# Microcontroller_and_Memory.net
KiCad netlist of a schematic drawn in Altium Designer
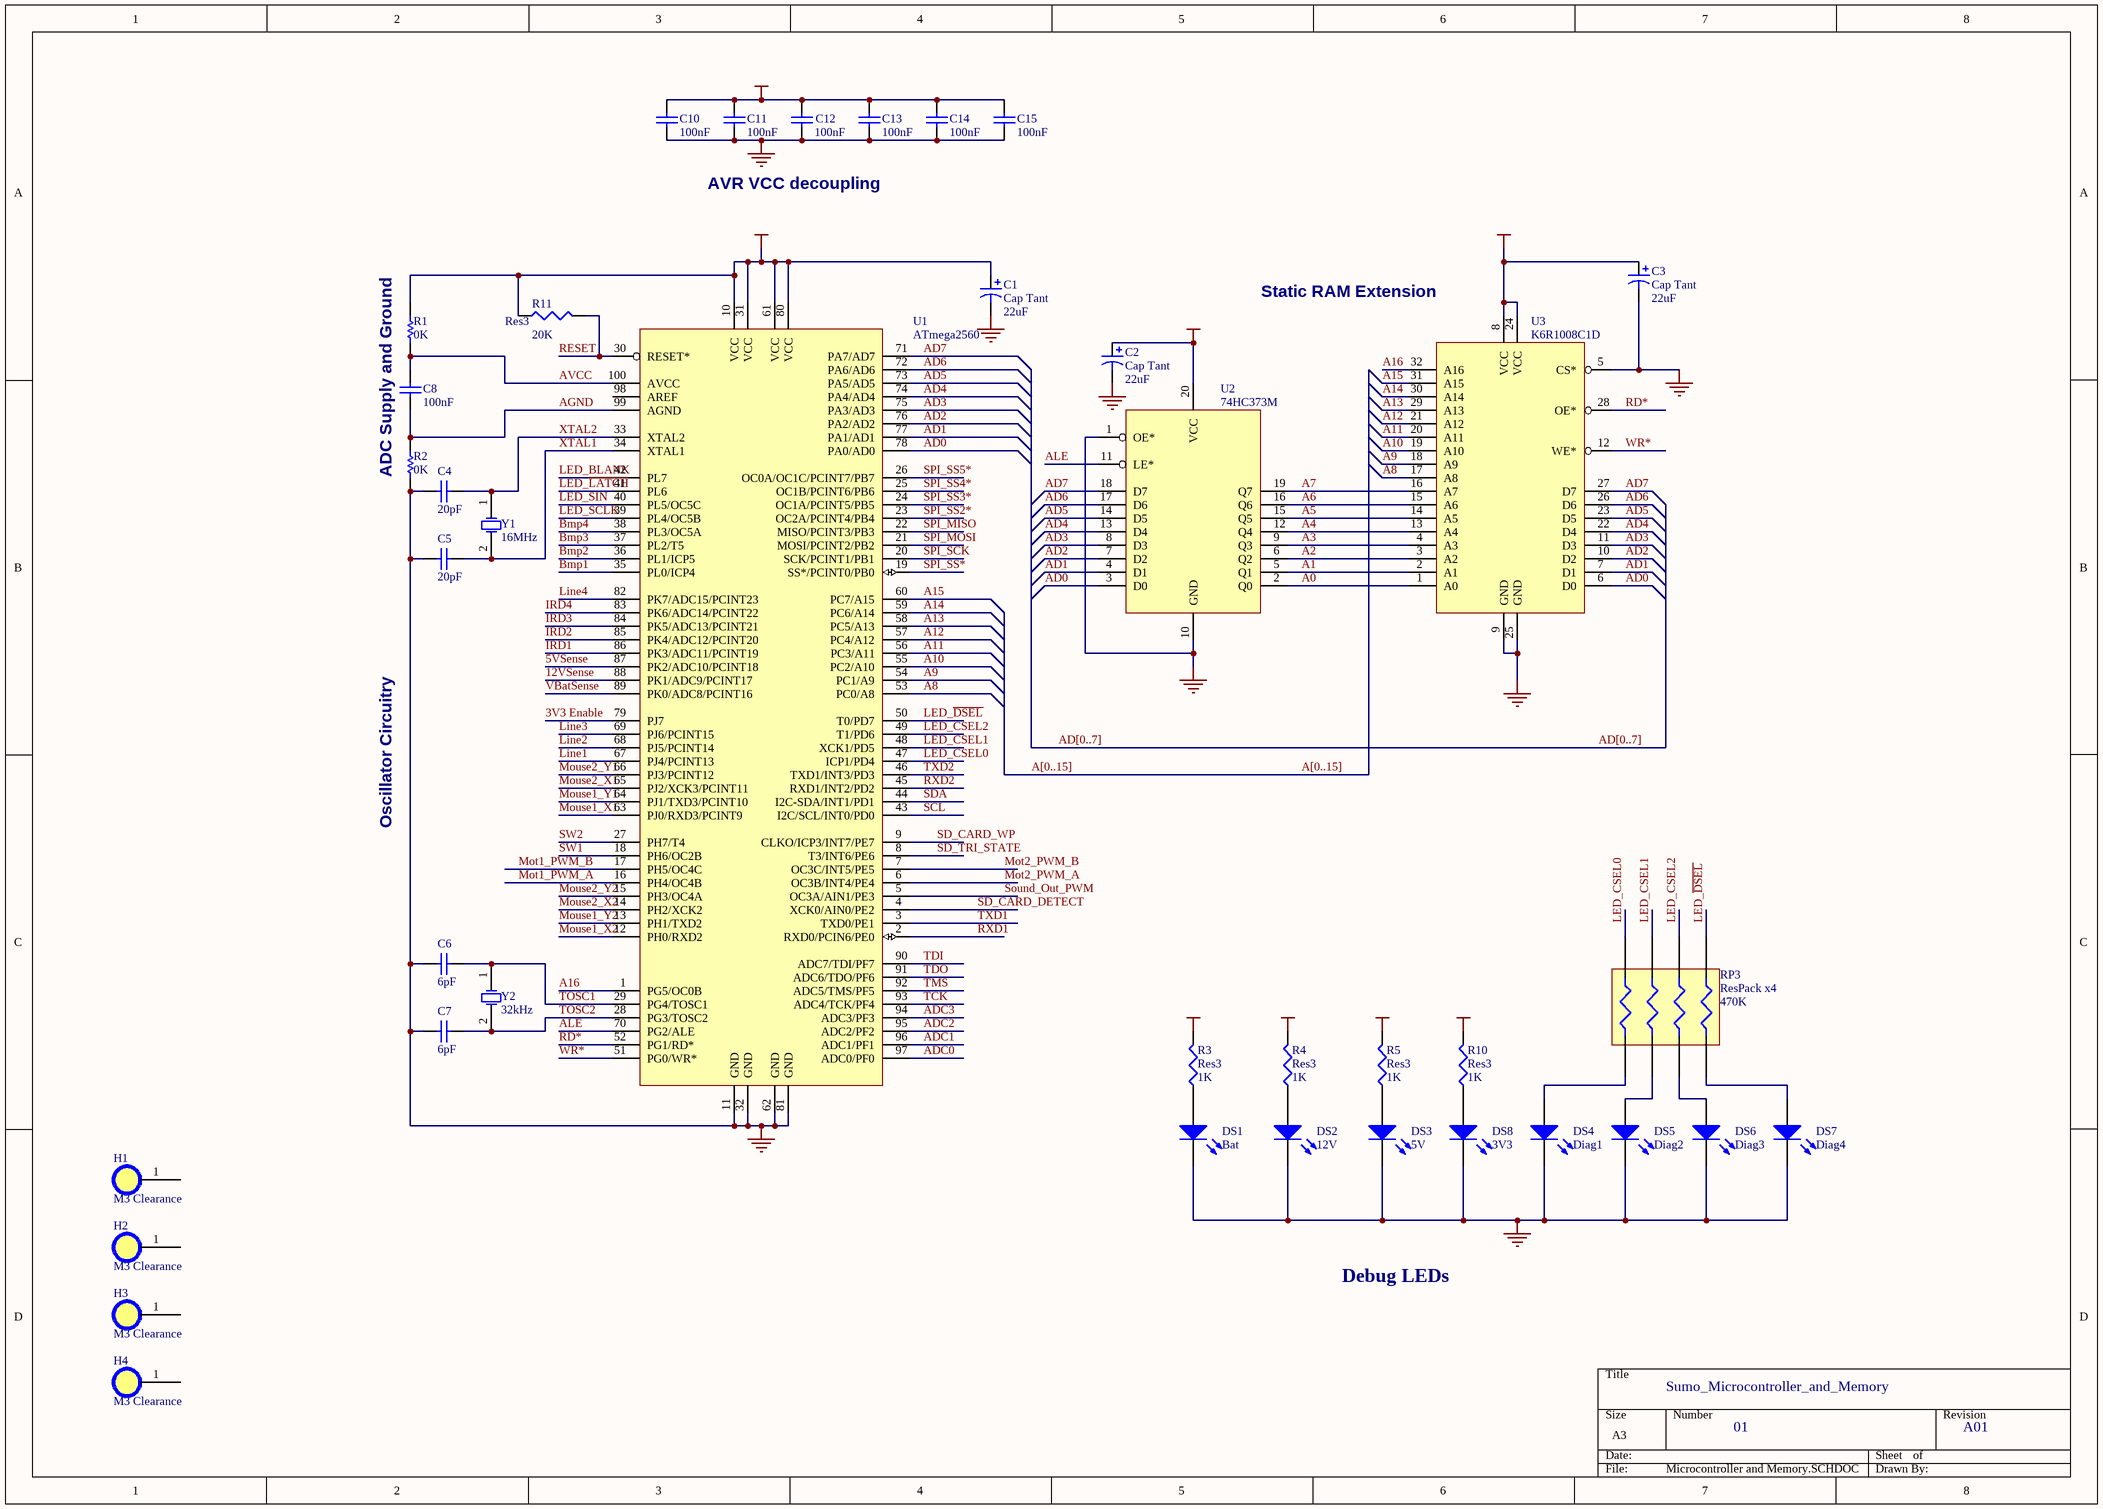
[diagram p0: Microcontroller and Memory.SCHDOC]

(export (version "E")
  (design (tool "Eeschema 10.0.6"))
  (components
    (comp (ref "C1")
      (value "Cap Tant")
      (footprint "CC4532-1812")
      (description "Polarized Capacitor (Axial)")
      (fields (field (name "ALTIUM_VALUE") "22uF") (field (name "PUBLISHER") "Altium Limited"))
      (libsource (lib "Miscellaneous Devices") (part "Cap Pol2"))
    )
    (comp (ref "C2")
      (value "Cap Tant")
      (footprint "CC4532-1812")
      (description "Polarized Capacitor (Axial)")
      (fields (field (name "ALTIUM_VALUE") "22uF") (field (name "PUBLISHER") "Altium Limited"))
      (libsource (lib "Miscellaneous Devices") (part "Cap Pol2"))
    )
    (comp (ref "C3")
      (value "Cap Tant")
      (footprint "CC4532-1812")
      (description "Polarized Capacitor (Axial)")
      (fields (field (name "ALTIUM_VALUE") "22uF") (field (name "PUBLISHER") "Altium Limited"))
      (libsource (lib "Miscellaneous Devices") (part "Cap Pol2"))
    )
    (comp (ref "C4")
      (value "20pF")
      (footprint "CC2012-0805")
      (description "Capacitor")
      (fields (field (name "PUBLISHER") "Altium Limited"))
      (libsource (lib "Miscellaneous Devices") (part "Cap"))
    )
    (comp (ref "C5")
      (value "20pF")
      (footprint "CC2012-0805")
      (description "Capacitor")
      (fields (field (name "PUBLISHER") "Altium Limited"))
      (libsource (lib "Miscellaneous Devices") (part "Cap"))
    )
    (comp (ref "C6")
      (value "6pF")
      (footprint "CC2012-0805")
      (description "Capacitor")
      (fields (field (name "PUBLISHER") "Altium Limited"))
      (libsource (lib "Miscellaneous Devices") (part "Cap"))
    )
    (comp (ref "C7")
      (value "6pF")
      (footprint "CC2012-0805")
      (description "Capacitor")
      (fields (field (name "PUBLISHER") "Altium Limited"))
      (libsource (lib "Miscellaneous Devices") (part "Cap"))
    )
    (comp (ref "C8")
      (value "100nF")
      (footprint "CC2012-0805")
      (description "Capacitor")
      (fields (field (name "PUBLISHER") "Altium Limited"))
      (libsource (lib "Miscellaneous Devices") (part "Cap"))
    )
    (comp (ref "C10")
      (value "100nF")
      (footprint "CC2012-0805")
      (description "Capacitor (Semiconductor SIM Model)")
      (fields (field (name "Comment") "Cap Semi") (field (name "PUBLISHER") "Altium Limited"))
      (libsource (lib "Miscellaneous Devices") (part "Cap Semi"))
    )
    (comp (ref "C11")
      (value "100nF")
      (footprint "CC2012-0805")
      (description "Capacitor (Semiconductor SIM Model)")
      (fields (field (name "Comment") "Cap Semi") (field (name "PUBLISHER") "Altium Limited"))
      (libsource (lib "Miscellaneous Devices") (part "Cap Semi"))
    )
    (comp (ref "C12")
      (value "100nF")
      (footprint "CC2012-0805")
      (description "Capacitor (Semiconductor SIM Model)")
      (fields (field (name "Comment") "Cap Semi") (field (name "PUBLISHER") "Altium Limited"))
      (libsource (lib "Miscellaneous Devices") (part "Cap Semi"))
    )
    (comp (ref "C13")
      (value "100nF")
      (footprint "CC2012-0805")
      (description "Capacitor (Semiconductor SIM Model)")
      (fields (field (name "Comment") "Cap Semi") (field (name "PUBLISHER") "Altium Limited"))
      (libsource (lib "Miscellaneous Devices") (part "Cap Semi"))
    )
    (comp (ref "C14")
      (value "100nF")
      (footprint "CC2012-0805")
      (description "Capacitor (Semiconductor SIM Model)")
      (fields (field (name "Comment") "Cap Semi") (field (name "PUBLISHER") "Altium Limited"))
      (libsource (lib "Miscellaneous Devices") (part "Cap Semi"))
    )
    (comp (ref "C15")
      (value "100nF")
      (footprint "CC2012-0805")
      (description "Capacitor (Semiconductor SIM Model)")
      (fields (field (name "Comment") "Cap Semi") (field (name "PUBLISHER") "Altium Limited"))
      (libsource (lib "Miscellaneous Devices") (part "Cap Semi"))
    )
    (comp (ref "DS1")
      (value "Bat")
      (footprint "SMD _LED")
      (description "Typical BLUE SiC LED")
      (fields (field (name "PUBLISHER") "Altium Limited"))
      (libsource (lib "Miscellaneous Devices") (part "LED3"))
    )
    (comp (ref "DS2")
      (value "12V")
      (footprint "SMD _LED")
      (description "Typical BLUE SiC LED")
      (fields (field (name "PUBLISHER") "Altium Limited"))
      (libsource (lib "Miscellaneous Devices") (part "LED3"))
    )
    (comp (ref "DS3")
      (value "5V")
      (footprint "SMD _LED")
      (description "Typical BLUE SiC LED")
      (fields (field (name "PUBLISHER") "Altium Limited"))
      (libsource (lib "Miscellaneous Devices") (part "LED3"))
    )
    (comp (ref "DS4")
      (value "Diag1")
      (footprint "SMD _LED")
      (description "Typical BLUE SiC LED")
      (fields (field (name "PUBLISHER") "Altium Limited"))
      (libsource (lib "Miscellaneous Devices") (part "LED3"))
    )
    (comp (ref "DS5")
      (value "Diag2")
      (footprint "SMD _LED")
      (description "Typical BLUE SiC LED")
      (fields (field (name "PUBLISHER") "Altium Limited"))
      (libsource (lib "Miscellaneous Devices") (part "LED3"))
    )
    (comp (ref "DS6")
      (value "Diag3")
      (footprint "SMD _LED")
      (description "Typical BLUE SiC LED")
      (fields (field (name "PUBLISHER") "Altium Limited"))
      (libsource (lib "Miscellaneous Devices") (part "LED3"))
    )
    (comp (ref "DS7")
      (value "Diag4")
      (footprint "SMD _LED")
      (description "Typical BLUE SiC LED")
      (fields (field (name "PUBLISHER") "Altium Limited"))
      (libsource (lib "Miscellaneous Devices") (part "LED3"))
    )
    (comp (ref "DS8")
      (value "3V3")
      (footprint "SMD _LED")
      (description "Typical BLUE SiC LED")
      (fields (field (name "PUBLISHER") "Altium Limited"))
      (libsource (lib "Miscellaneous Devices") (part "LED3"))
    )
    (comp (ref "H1")
      (value "M3 Clearance")
      (footprint "M3 Clearance")
      (description "3.2mm ID clearance hole for M3 screw")
      (libsource (lib "Sumo") (part "M3 Clearance hole"))
    )
    (comp (ref "H2")
      (value "M3 Clearance")
      (footprint "M3 Clearance")
      (description "3.2mm ID clearance hole for M3 screw")
      (libsource (lib "Sumo") (part "M3 Clearance hole"))
    )
    (comp (ref "H3")
      (value "M3 Clearance")
      (footprint "M3 Clearance")
      (description "3.2mm ID clearance hole for M3 screw")
      (libsource (lib "Sumo") (part "M3 Clearance hole"))
    )
    (comp (ref "H4")
      (value "M3 Clearance")
      (footprint "M3 Clearance")
      (description "3.2mm ID clearance hole for M3 screw")
      (libsource (lib "Sumo") (part "M3 Clearance hole"))
    )
    (comp (ref "R1")
      (value "0K")
      (footprint "R2012-0805")
      (description "Resistor")
      (fields (field (name "PUBLISHER") "Altium Limited"))
      (libsource (lib "Miscellaneous Devices") (part "Res1"))
    )
    (comp (ref "R2")
      (value "0K")
      (footprint "R2012-0805")
      (description "Resistor")
      (fields (field (name "PUBLISHER") "Altium Limited"))
      (libsource (lib "Miscellaneous Devices") (part "Res1"))
    )
    (comp (ref "R3")
      (value "Res3")
      (footprint "R2012-0805")
      (description "Resistor")
      (fields (field (name "ALTIUM_VALUE") "1K") (field (name "PUBLISHER") "Altium Limited"))
      (libsource (lib "Miscellaneous Devices") (part "Res3"))
    )
    (comp (ref "R4")
      (value "Res3")
      (footprint "R2012-0805")
      (description "Resistor")
      (fields (field (name "ALTIUM_VALUE") "1K") (field (name "PUBLISHER") "Altium Limited"))
      (libsource (lib "Miscellaneous Devices") (part "Res3"))
    )
    (comp (ref "R5")
      (value "Res3")
      (footprint "R2012-0805")
      (description "Resistor")
      (fields (field (name "ALTIUM_VALUE") "1K") (field (name "PUBLISHER") "Altium Limited"))
      (libsource (lib "Miscellaneous Devices") (part "Res3"))
    )
    (comp (ref "R10")
      (value "Res3")
      (footprint "R2012-0805")
      (description "Resistor")
      (fields (field (name "ALTIUM_VALUE") "1K") (field (name "PUBLISHER") "Altium Limited"))
      (libsource (lib "Miscellaneous Devices") (part "Res3"))
    )
    (comp (ref "R11")
      (value "Res3")
      (footprint "R2012-0805")
      (description "Resistor")
      (fields (field (name "ALTIUM_VALUE") "20K") (field (name "PUBLISHER") "Altium Limited"))
      (libsource (lib "Miscellaneous Devices") (part "Res3"))
    )
    (comp (ref "RP3")
      (value "ResPack x4")
      (footprint "4x0805 Resistor pack")
      (fields (field (name "ALTIUM_VALUE") "470K"))
      (libsource (lib "Sumo") (part "ResPack x4"))
    )
    (comp (ref "U1")
      (value "ATmega2560")
      (footprint "F-QFP14X14-G100/Z17N")
      (description "Atmel ATmega2560 MCU")
      (libsource (lib "Sumo") (part "ATmega2560"))
    )
    (comp (ref "U2")
      (value "74HC373M")
      (footprint "SO-G20/Y1.45")
      (description "Octal 8-bit D-type Latch")
      (libsource (lib "Schematic Library") (part "74373"))
    )
    (comp (ref "U3")
      (value "K6R1008C1D")
      (footprint "SO-G32/Y1.45")
      (description "Samsung 128Kx8 High-Speed Static RAM")
      (libsource (lib "Schematic Library") (part "K6R1008C1D"))
    )
    (comp (ref "Y1")
      (value "16MHz")
      (footprint "Crystal HC49SLF")
      (description "Crystal Oscillator")
      (fields (field (name "PUBLISHER") "Altium Limited"))
      (libsource (lib "Miscellaneous Devices") (part "XTAL"))
    )
    (comp (ref "Y2")
      (value "32kHz")
      (footprint "Crystal CFS206")
      (description "Crystal Oscillator")
      (fields (field (name "PUBLISHER") "Altium Limited"))
      (libsource (lib "Miscellaneous Devices") (part "XTAL"))
    )
  )
  (nets
    (net (code "1") (name "/3V3 Enable") (class "Default")
      (node (ref "U1") (pin "79") (pinfunction "PJ7_79") (pintype "passive"))
    )
    (net (code "2") (name "/5VSense") (class "Default")
      (node (ref "U1") (pin "87") (pinfunction "PK2/ADC10/PCINT18_87") (pintype "passive"))
    )
    (net (code "3") (name "/12VSense") (class "Default")
      (node (ref "U1") (pin "88") (pinfunction "PK1/ADC9/PCINT17_88") (pintype "passive"))
    )
    (net (code "4") (name "/A0") (class "Default")
      (node (ref "U2") (pin "2") (pinfunction "Q0_2") (pintype "passive"))
      (node (ref "U3") (pin "1") (pinfunction "A0_1") (pintype "passive"))
    )
    (net (code "5") (name "/A1") (class "Default")
      (node (ref "U2") (pin "5") (pinfunction "Q1_5") (pintype "passive"))
      (node (ref "U3") (pin "2") (pinfunction "A1_2") (pintype "passive"))
    )
    (net (code "6") (name "/A2") (class "Default")
      (node (ref "U2") (pin "6") (pinfunction "Q2_6") (pintype "passive"))
      (node (ref "U3") (pin "3") (pinfunction "A2_3") (pintype "passive"))
    )
    (net (code "7") (name "/A3") (class "Default")
      (node (ref "U2") (pin "9") (pinfunction "Q3_9") (pintype "passive"))
      (node (ref "U3") (pin "4") (pinfunction "A3_4") (pintype "passive"))
    )
    (net (code "8") (name "/A4") (class "Default")
      (node (ref "U2") (pin "12") (pinfunction "Q4_12") (pintype "passive"))
      (node (ref "U3") (pin "13") (pinfunction "A4_13") (pintype "passive"))
    )
    (net (code "9") (name "/A5") (class "Default")
      (node (ref "U2") (pin "15") (pinfunction "Q5_15") (pintype "passive"))
      (node (ref "U3") (pin "14") (pinfunction "A5_14") (pintype "passive"))
    )
    (net (code "10") (name "/A6") (class "Default")
      (node (ref "U2") (pin "16") (pinfunction "Q6_16") (pintype "passive"))
      (node (ref "U3") (pin "15") (pinfunction "A6_15") (pintype "passive"))
    )
    (net (code "11") (name "/A7") (class "Default")
      (node (ref "U2") (pin "19") (pinfunction "Q7_19") (pintype "passive"))
      (node (ref "U3") (pin "16") (pinfunction "A7_16") (pintype "passive"))
    )
    (net (code "12") (name "/A8") (class "Default")
      (node (ref "U1") (pin "53") (pinfunction "PC0/A8_53") (pintype "passive"))
      (node (ref "U3") (pin "17") (pinfunction "A8_17") (pintype "passive"))
    )
    (net (code "13") (name "/A9") (class "Default")
      (node (ref "U1") (pin "54") (pinfunction "PC1/A9_54") (pintype "passive"))
      (node (ref "U3") (pin "18") (pinfunction "A9_18") (pintype "passive"))
    )
    (net (code "14") (name "/A10") (class "Default")
      (node (ref "U1") (pin "55") (pinfunction "PC2/A10_55") (pintype "passive"))
      (node (ref "U3") (pin "19") (pinfunction "A10_19") (pintype "passive"))
    )
    (net (code "15") (name "/A11") (class "Default")
      (node (ref "U1") (pin "56") (pinfunction "PC3/A11_56") (pintype "passive"))
      (node (ref "U3") (pin "20") (pinfunction "A11_20") (pintype "passive"))
    )
    (net (code "16") (name "/A12") (class "Default")
      (node (ref "U1") (pin "57") (pinfunction "PC4/A12_57") (pintype "passive"))
      (node (ref "U3") (pin "21") (pinfunction "A12_21") (pintype "passive"))
    )
    (net (code "17") (name "/A13") (class "Default")
      (node (ref "U1") (pin "58") (pinfunction "PC5/A13_58") (pintype "passive"))
      (node (ref "U3") (pin "29") (pinfunction "A13_29") (pintype "passive"))
    )
    (net (code "18") (name "/A14") (class "Default")
      (node (ref "U1") (pin "59") (pinfunction "PC6/A14_59") (pintype "passive"))
      (node (ref "U3") (pin "30") (pinfunction "A14_30") (pintype "passive"))
    )
    (net (code "19") (name "/A15") (class "Default")
      (node (ref "U1") (pin "60") (pinfunction "PC7/A15_60") (pintype "passive"))
      (node (ref "U3") (pin "31") (pinfunction "A15_31") (pintype "passive"))
    )
    (net (code "20") (name "/A16") (class "Default")
      (node (ref "U1") (pin "1") (pinfunction "PG5/OC0B_1") (pintype "passive"))
      (node (ref "U3") (pin "32") (pinfunction "A16_32") (pintype "passive"))
    )
    (net (code "21") (name "/AD0") (class "Default")
      (node (ref "U1") (pin "78") (pinfunction "PA0/AD0_78") (pintype "passive"))
      (node (ref "U2") (pin "3") (pinfunction "D0_3") (pintype "passive"))
      (node (ref "U3") (pin "6") (pinfunction "D0_6") (pintype "passive"))
    )
    (net (code "22") (name "/AD1") (class "Default")
      (node (ref "U1") (pin "77") (pinfunction "PA1/AD1_77") (pintype "passive"))
      (node (ref "U2") (pin "4") (pinfunction "D1_4") (pintype "passive"))
      (node (ref "U3") (pin "7") (pinfunction "D1_7") (pintype "passive"))
    )
    (net (code "23") (name "/AD2") (class "Default")
      (node (ref "U1") (pin "76") (pinfunction "PA2/AD2_76") (pintype "passive"))
      (node (ref "U2") (pin "7") (pinfunction "D2_7") (pintype "passive"))
      (node (ref "U3") (pin "10") (pinfunction "D2_10") (pintype "passive"))
    )
    (net (code "24") (name "/AD3") (class "Default")
      (node (ref "U1") (pin "75") (pinfunction "PA3/AD3_75") (pintype "passive"))
      (node (ref "U2") (pin "8") (pinfunction "D3_8") (pintype "passive"))
      (node (ref "U3") (pin "11") (pinfunction "D3_11") (pintype "passive"))
    )
    (net (code "25") (name "/AD4") (class "Default")
      (node (ref "U1") (pin "74") (pinfunction "PA4/AD4_74") (pintype "passive"))
      (node (ref "U2") (pin "13") (pinfunction "D4_13") (pintype "passive"))
      (node (ref "U3") (pin "22") (pinfunction "D4_22") (pintype "passive"))
    )
    (net (code "26") (name "/AD5") (class "Default")
      (node (ref "U1") (pin "73") (pinfunction "PA5/AD5_73") (pintype "passive"))
      (node (ref "U2") (pin "14") (pinfunction "D5_14") (pintype "passive"))
      (node (ref "U3") (pin "23") (pinfunction "D5_23") (pintype "passive"))
    )
    (net (code "27") (name "/AD6") (class "Default")
      (node (ref "U1") (pin "72") (pinfunction "PA6/AD6_72") (pintype "passive"))
      (node (ref "U2") (pin "17") (pinfunction "D6_17") (pintype "passive"))
      (node (ref "U3") (pin "26") (pinfunction "D6_26") (pintype "passive"))
    )
    (net (code "28") (name "/AD7") (class "Default")
      (node (ref "U1") (pin "71") (pinfunction "PA7/AD7_71") (pintype "passive"))
      (node (ref "U2") (pin "18") (pinfunction "D7_18") (pintype "passive"))
      (node (ref "U3") (pin "27") (pinfunction "D7_27") (pintype "passive"))
    )
    (net (code "29") (name "/ADC0") (class "Default")
      (node (ref "U1") (pin "97") (pinfunction "ADC0/PF0_97") (pintype "passive"))
    )
    (net (code "30") (name "/ADC1") (class "Default")
      (node (ref "U1") (pin "96") (pinfunction "ADC1/PF1_96") (pintype "passive"))
    )
    (net (code "31") (name "/ADC2") (class "Default")
      (node (ref "U1") (pin "95") (pinfunction "ADC2/PF2_95") (pintype "passive"))
    )
    (net (code "32") (name "/ADC3") (class "Default")
      (node (ref "U1") (pin "94") (pinfunction "ADC3/PF3_94") (pintype "passive"))
    )
    (net (code "34") (name "/AGND") (class "Default")
      (node (ref "C8") (pin "2") (pinfunction "2_2") (pintype "passive"))
      (node (ref "R2") (pin "2") (pinfunction "2_2") (pintype "passive"))
      (node (ref "U1") (pin "99") (pinfunction "AGND_99") (pintype "passive"))
    )
    (net (code "35") (name "/ALE") (class "Default")
      (node (ref "U1") (pin "70") (pinfunction "PG2/ALE_70") (pintype "passive"))
      (node (ref "U2") (pin "11") (pinfunction "LE*_11") (pintype "passive"))
    )
    (net (code "36") (name "/AVCC") (class "Default")
      (node (ref "C8") (pin "1") (pinfunction "1_1") (pintype "passive"))
      (node (ref "R1") (pin "1") (pinfunction "1_1") (pintype "passive"))
      (node (ref "U1") (pin "100") (pinfunction "AVCC_100") (pintype "passive"))
    )
    (net (code "38") (name "/Bmp1") (class "Default")
      (node (ref "U1") (pin "35") (pinfunction "PL0/ICP4_35") (pintype "passive"))
    )
    (net (code "39") (name "/Bmp2") (class "Default")
      (node (ref "U1") (pin "36") (pinfunction "PL1/ICP5_36") (pintype "passive"))
    )
    (net (code "40") (name "/Bmp3") (class "Default")
      (node (ref "U1") (pin "37") (pinfunction "PL2/T5_37") (pintype "passive"))
    )
    (net (code "41") (name "/Bmp4") (class "Default")
      (node (ref "U1") (pin "38") (pinfunction "PL3/OC5A_38") (pintype "passive"))
    )
    (net (code "42") (name "/IRD1") (class "Default")
      (node (ref "U1") (pin "86") (pinfunction "PK3/ADC11/PCINT19_86") (pintype "passive"))
    )
    (net (code "43") (name "/IRD2") (class "Default")
      (node (ref "U1") (pin "85") (pinfunction "PK4/ADC12/PCINT20_85") (pintype "passive"))
    )
    (net (code "44") (name "/IRD3") (class "Default")
      (node (ref "U1") (pin "84") (pinfunction "PK5/ADC13/PCINT21_84") (pintype "passive"))
    )
    (net (code "45") (name "/IRD4") (class "Default")
      (node (ref "U1") (pin "83") (pinfunction "PK6/ADC14/PCINT22_83") (pintype "passive"))
    )
    (net (code "46") (name "/LED_BLANK") (class "Default")
      (node (ref "U1") (pin "42") (pinfunction "PL7_42") (pintype "passive"))
    )
    (net (code "47") (name "/LED_CSEL0") (class "Default")
      (node (ref "RP3") (pin "8") (pintype "passive"))
      (node (ref "U1") (pin "47") (pinfunction "ICP1/PD4_47") (pintype "passive"))
    )
    (net (code "48") (name "/LED_CSEL1") (class "Default")
      (node (ref "RP3") (pin "7") (pintype "passive"))
      (node (ref "U1") (pin "48") (pinfunction "XCK1/PD5_48") (pintype "passive"))
    )
    (net (code "49") (name "/LED_CSEL2") (class "Default")
      (node (ref "RP3") (pin "6") (pintype "passive"))
      (node (ref "U1") (pin "49") (pinfunction "T1/PD6_49") (pintype "passive"))
    )
    (net (code "50") (name "/LED_SCLK") (class "Default")
      (node (ref "U1") (pin "39") (pinfunction "PL4/OC5B_39") (pintype "passive"))
    )
    (net (code "51") (name "/LED_SIN") (class "Default")
      (node (ref "U1") (pin "40") (pinfunction "PL5/OC5C_40") (pintype "passive"))
    )
    (net (code "52") (name "/LED_~{DSEL}") (class "Default")
      (node (ref "RP3") (pin "5") (pintype "passive"))
      (node (ref "U1") (pin "50") (pinfunction "T0/PD7_50") (pintype "passive"))
    )
    (net (code "53") (name "/LED_~{LATCH}") (class "Default")
      (node (ref "U1") (pin "41") (pinfunction "PL6_41") (pintype "passive"))
    )
    (net (code "54") (name "/Line1") (class "Default")
      (node (ref "U1") (pin "67") (pinfunction "PJ4/PCINT13_67") (pintype "passive"))
    )
    (net (code "55") (name "/Line2") (class "Default")
      (node (ref "U1") (pin "68") (pinfunction "PJ5/PCINT14_68") (pintype "passive"))
    )
    (net (code "56") (name "/Line3") (class "Default")
      (node (ref "U1") (pin "69") (pinfunction "PJ6/PCINT15_69") (pintype "passive"))
    )
    (net (code "57") (name "/Line4") (class "Default")
      (node (ref "U1") (pin "82") (pinfunction "PK7/ADC15/PCINT23_82") (pintype "passive"))
    )
    (net (code "58") (name "/Mot1_PWM_A") (class "Default")
      (node (ref "U1") (pin "16") (pinfunction "PH4/OC4B_16") (pintype "passive"))
    )
    (net (code "59") (name "/Mot1_PWM_B") (class "Default")
      (node (ref "U1") (pin "17") (pinfunction "PH5/OC4C_17") (pintype "passive"))
    )
    (net (code "60") (name "/Mot2_PWM_A") (class "Default")
      (node (ref "U1") (pin "6") (pinfunction "OC3B/INT4/PE4_6") (pintype "passive"))
    )
    (net (code "61") (name "/Mot2_PWM_B") (class "Default")
      (node (ref "U1") (pin "7") (pinfunction "OC3C/INT5/PE5_7") (pintype "passive"))
    )
    (net (code "62") (name "/Mouse1_X1") (class "Default")
      (node (ref "U1") (pin "63") (pinfunction "PJ0/RXD3/PCINT9_63") (pintype "passive"))
    )
    (net (code "63") (name "/Mouse1_X2") (class "Default")
      (node (ref "U1") (pin "12") (pinfunction "PH0/RXD2_12") (pintype "passive"))
    )
    (net (code "64") (name "/Mouse1_Y1") (class "Default")
      (node (ref "U1") (pin "64") (pinfunction "PJ1/TXD3/PCINT10_64") (pintype "passive"))
    )
    (net (code "65") (name "/Mouse1_Y2") (class "Default")
      (node (ref "U1") (pin "13") (pinfunction "PH1/TXD2_13") (pintype "passive"))
    )
    (net (code "66") (name "/Mouse2_X1") (class "Default")
      (node (ref "U1") (pin "65") (pinfunction "PJ2/XCK3/PCINT11_65") (pintype "passive"))
    )
    (net (code "67") (name "/Mouse2_X2") (class "Default")
      (node (ref "U1") (pin "14") (pinfunction "PH2/XCK2_14") (pintype "passive"))
    )
    (net (code "68") (name "/Mouse2_Y1") (class "Default")
      (node (ref "U1") (pin "66") (pinfunction "PJ3/PCINT12_66") (pintype "passive"))
    )
    (net (code "69") (name "/Mouse2_Y2") (class "Default")
      (node (ref "U1") (pin "15") (pinfunction "PH3/OC4A_15") (pintype "passive"))
    )
    (net (code "70") (name "/RD*") (class "Default")
      (node (ref "U1") (pin "52") (pinfunction "PG1/RD*_52") (pintype "passive"))
      (node (ref "U3") (pin "28") (pinfunction "OE*_28") (pintype "passive"))
    )
    (net (code "71") (name "/RESET") (class "Default")
      (node (ref "R11") (pin "2") (pinfunction "2_2") (pintype "passive"))
      (node (ref "U1") (pin "30") (pinfunction "RESET*_30") (pintype "passive"))
    )
    (net (code "72") (name "/RXD1") (class "Default")
      (node (ref "U1") (pin "2") (pinfunction "RXD0/PCIN6/PE0_2") (pintype "bidirectional"))
    )
    (net (code "73") (name "/RXD2") (class "Default")
      (node (ref "U1") (pin "45") (pinfunction "RXD1/INT2/PD2_45") (pintype "passive"))
    )
    (net (code "74") (name "/SCL") (class "Default")
      (node (ref "U1") (pin "43") (pinfunction "I2C/SCL/INT0/PD0_43") (pintype "passive"))
    )
    (net (code "75") (name "/SDA") (class "Default")
      (node (ref "U1") (pin "44") (pinfunction "I2C-SDA/INT1/PD1_44") (pintype "passive"))
    )
    (net (code "76") (name "/SD_CARD_DETECT") (class "Default")
      (node (ref "U1") (pin "4") (pinfunction "XCK0/AIN0/PE2_4") (pintype "passive"))
    )
    (net (code "77") (name "/SD_CARD_WP") (class "Default")
      (node (ref "U1") (pin "9") (pinfunction "CLKO/ICP3/INT7/PE7_9") (pintype "passive"))
    )
    (net (code "78") (name "/SD_TRI_STATE") (class "Default")
      (node (ref "U1") (pin "8") (pinfunction "T3/INT6/PE6_8") (pintype "passive"))
    )
    (net (code "79") (name "/SPI_MISO") (class "Default")
      (node (ref "U1") (pin "22") (pinfunction "MISO/PCINT3/PB3_22") (pintype "passive"))
    )
    (net (code "80") (name "/SPI_MOSI") (class "Default")
      (node (ref "U1") (pin "21") (pinfunction "MOSI/PCINT2/PB2_21") (pintype "passive"))
    )
    (net (code "81") (name "/SPI_SCK") (class "Default")
      (node (ref "U1") (pin "20") (pinfunction "SCK/PCINT1/PB1_20") (pintype "passive"))
    )
    (net (code "82") (name "/SPI_SS*") (class "Default")
      (node (ref "U1") (pin "19") (pinfunction "SS*/PCINT0/PB0_19") (pintype "bidirectional"))
    )
    (net (code "83") (name "/SPI_SS2*") (class "Default")
      (node (ref "U1") (pin "23") (pinfunction "OC2A/PCINT4/PB4_23") (pintype "passive"))
    )
    (net (code "84") (name "/SPI_SS3*") (class "Default")
      (node (ref "U1") (pin "24") (pinfunction "OC1A/PCINT5/PB5_24") (pintype "passive"))
    )
    (net (code "85") (name "/SPI_SS4*") (class "Default")
      (node (ref "U1") (pin "25") (pinfunction "OC1B/PCINT6/PB6_25") (pintype "passive"))
    )
    (net (code "86") (name "/SPI_SS5*") (class "Default")
      (node (ref "U1") (pin "26") (pinfunction "OC0A/OC1C/PCINT7/PB7_26") (pintype "passive"))
    )
    (net (code "87") (name "/SW1") (class "Default")
      (node (ref "U1") (pin "18") (pinfunction "PH6/OC2B_18") (pintype "passive"))
    )
    (net (code "88") (name "/SW2") (class "Default")
      (node (ref "U1") (pin "27") (pinfunction "PH7/T4_27") (pintype "passive"))
    )
    (net (code "89") (name "/Sound_Out_PWM") (class "Default")
      (node (ref "U1") (pin "5") (pinfunction "OC3A/AIN1/PE3_5") (pintype "passive"))
    )
    (net (code "90") (name "/TCK") (class "Default")
      (node (ref "U1") (pin "93") (pinfunction "ADC4/TCK/PF4_93") (pintype "passive"))
    )
    (net (code "91") (name "/TDI") (class "Default")
      (node (ref "U1") (pin "90") (pinfunction "ADC7/TDI/PF7_90") (pintype "passive"))
    )
    (net (code "92") (name "/TDO") (class "Default")
      (node (ref "U1") (pin "91") (pinfunction "ADC6/TDO/PF6_91") (pintype "passive"))
    )
    (net (code "93") (name "/TMS") (class "Default")
      (node (ref "U1") (pin "92") (pinfunction "ADC5/TMS/PF5_92") (pintype "passive"))
    )
    (net (code "94") (name "/TOSC1") (class "Default")
      (node (ref "C6") (pin "2") (pinfunction "2_2") (pintype "passive"))
      (node (ref "U1") (pin "29") (pinfunction "PG4/TOSC1_29") (pintype "passive"))
      (node (ref "Y2") (pin "1") (pinfunction "OSC1_1") (pintype "passive"))
    )
    (net (code "95") (name "/TOSC2") (class "Default")
      (node (ref "C7") (pin "2") (pinfunction "2_2") (pintype "passive"))
      (node (ref "U1") (pin "28") (pinfunction "PG3/TOSC2_28") (pintype "passive"))
      (node (ref "Y2") (pin "2") (pinfunction "OSC2_2") (pintype "passive"))
    )
    (net (code "96") (name "/TXD1") (class "Default")
      (node (ref "U1") (pin "3") (pinfunction "TXD0/PE1_3") (pintype "passive"))
    )
    (net (code "97") (name "/TXD2") (class "Default")
      (node (ref "U1") (pin "46") (pinfunction "TXD1/INT3/PD3_46") (pintype "passive"))
    )
    (net (code "98") (name "/VBatSense") (class "Default")
      (node (ref "U1") (pin "89") (pinfunction "PK0/ADC8/PCINT16_89") (pintype "passive"))
    )
    (net (code "99") (name "/WR*") (class "Default")
      (node (ref "U1") (pin "51") (pinfunction "PG0/WR*_51") (pintype "passive"))
      (node (ref "U3") (pin "12") (pinfunction "WE*_12") (pintype "passive"))
    )
    (net (code "100") (name "/XTAL1") (class "Default")
      (node (ref "C5") (pin "2") (pinfunction "2_2") (pintype "passive"))
      (node (ref "U1") (pin "34") (pinfunction "XTAL1_34") (pintype "passive"))
      (node (ref "Y1") (pin "2") (pinfunction "OSC2_2") (pintype "passive"))
    )
    (net (code "101") (name "/XTAL2") (class "Default")
      (node (ref "C4") (pin "2") (pinfunction "2_2") (pintype "passive"))
      (node (ref "U1") (pin "33") (pinfunction "XTAL2_33") (pintype "passive"))
      (node (ref "Y1") (pin "1") (pinfunction "OSC1_1") (pintype "passive"))
    )
    (net (code "102") (name "3V3") (class "Default")
      (node (ref "R10") (pin "2") (pinfunction "2_2") (pintype "passive"))
    )
    (net (code "103") (name "5V") (class "Default")
      (node (ref "C1") (pin "1") (pinfunction "1_1") (pintype "passive"))
      (node (ref "C10") (pin "2") (pinfunction "2_2") (pintype "passive"))
      (node (ref "C11") (pin "2") (pinfunction "2_2") (pintype "passive"))
      (node (ref "C12") (pin "2") (pinfunction "2_2") (pintype "passive"))
      (node (ref "C13") (pin "2") (pinfunction "2_2") (pintype "passive"))
      (node (ref "C14") (pin "2") (pinfunction "2_2") (pintype "passive"))
      (node (ref "C15") (pin "2") (pinfunction "2_2") (pintype "passive"))
      (node (ref "C2") (pin "1") (pinfunction "1_1") (pintype "passive"))
      (node (ref "C3") (pin "1") (pinfunction "1_1") (pintype "passive"))
      (node (ref "R1") (pin "2") (pinfunction "2_2") (pintype "passive"))
      (node (ref "R11") (pin "1") (pinfunction "1_1") (pintype "passive"))
      (node (ref "R5") (pin "2") (pinfunction "2_2") (pintype "passive"))
      (node (ref "U1") (pin "10") (pinfunction "VCC_10") (pintype "passive"))
      (node (ref "U1") (pin "31") (pinfunction "VCC_31") (pintype "passive"))
      (node (ref "U1") (pin "61") (pinfunction "VCC_61") (pintype "passive"))
      (node (ref "U1") (pin "80") (pinfunction "VCC_80") (pintype "passive"))
      (node (ref "U2") (pin "20") (pinfunction "VCC_20") (pintype "passive"))
      (node (ref "U3") (pin "24") (pinfunction "VCC_24") (pintype "passive"))
      (node (ref "U3") (pin "8") (pinfunction "VCC_8") (pintype "passive"))
    )
    (net (code "104") (name "12V") (class "Default")
      (node (ref "R4") (pin "2") (pinfunction "2_2") (pintype "passive"))
    )
    (net (code "105") (name "GND") (class "Default")
      (node (ref "C1") (pin "2") (pinfunction "2_2") (pintype "passive"))
      (node (ref "C10") (pin "1") (pinfunction "1_1") (pintype "passive"))
      (node (ref "C11") (pin "1") (pinfunction "1_1") (pintype "passive"))
      (node (ref "C12") (pin "1") (pinfunction "1_1") (pintype "passive"))
      (node (ref "C13") (pin "1") (pinfunction "1_1") (pintype "passive"))
      (node (ref "C14") (pin "1") (pinfunction "1_1") (pintype "passive"))
      (node (ref "C15") (pin "1") (pinfunction "1_1") (pintype "passive"))
      (node (ref "C2") (pin "2") (pinfunction "2_2") (pintype "passive"))
      (node (ref "C3") (pin "2") (pinfunction "2_2") (pintype "passive"))
      (node (ref "C4") (pin "1") (pinfunction "1_1") (pintype "passive"))
      (node (ref "C5") (pin "1") (pinfunction "1_1") (pintype "passive"))
      (node (ref "C6") (pin "1") (pinfunction "1_1") (pintype "passive"))
      (node (ref "C7") (pin "1") (pinfunction "1_1") (pintype "passive"))
      (node (ref "DS1") (pin "2") (pinfunction "K_2") (pintype "passive"))
      (node (ref "DS2") (pin "2") (pinfunction "K_2") (pintype "passive"))
      (node (ref "DS3") (pin "2") (pinfunction "K_2") (pintype "passive"))
      (node (ref "DS4") (pin "2") (pinfunction "K_2") (pintype "passive"))
      (node (ref "DS5") (pin "2") (pinfunction "K_2") (pintype "passive"))
      (node (ref "DS6") (pin "2") (pinfunction "K_2") (pintype "passive"))
      (node (ref "DS7") (pin "2") (pinfunction "K_2") (pintype "passive"))
      (node (ref "DS8") (pin "2") (pinfunction "K_2") (pintype "passive"))
      (node (ref "R2") (pin "1") (pinfunction "1_1") (pintype "passive"))
      (node (ref "U1") (pin "11") (pinfunction "GND_11") (pintype "passive"))
      (node (ref "U1") (pin "32") (pinfunction "GND_32") (pintype "passive"))
      (node (ref "U1") (pin "62") (pinfunction "GND_62") (pintype "passive"))
      (node (ref "U1") (pin "81") (pinfunction "GND_81") (pintype "passive"))
      (node (ref "U2") (pin "1") (pinfunction "OE*_1") (pintype "passive"))
      (node (ref "U2") (pin "10") (pinfunction "GND_10") (pintype "passive"))
      (node (ref "U3") (pin "25") (pinfunction "GND_25") (pintype "passive"))
      (node (ref "U3") (pin "5") (pinfunction "CS*_5") (pintype "passive"))
      (node (ref "U3") (pin "9") (pinfunction "GND_9") (pintype "passive"))
    )
    (net (code "106") (name "Net-(DS1-A)") (class "Default")
      (node (ref "DS1") (pin "1") (pinfunction "A_1") (pintype "passive"))
      (node (ref "R3") (pin "1") (pinfunction "1_1") (pintype "passive"))
    )
    (net (code "107") (name "Net-(DS2-A)") (class "Default")
      (node (ref "DS2") (pin "1") (pinfunction "A_1") (pintype "passive"))
      (node (ref "R4") (pin "1") (pinfunction "1_1") (pintype "passive"))
    )
    (net (code "108") (name "Net-(DS3-A)") (class "Default")
      (node (ref "DS3") (pin "1") (pinfunction "A_1") (pintype "passive"))
      (node (ref "R5") (pin "1") (pinfunction "1_1") (pintype "passive"))
    )
    (net (code "109") (name "Net-(DS4-A)") (class "Default")
      (node (ref "DS4") (pin "1") (pinfunction "A_1") (pintype "passive"))
      (node (ref "RP3") (pin "1") (pintype "passive"))
    )
    (net (code "110") (name "Net-(DS5-A)") (class "Default")
      (node (ref "DS5") (pin "1") (pinfunction "A_1") (pintype "passive"))
      (node (ref "RP3") (pin "2") (pintype "passive"))
    )
    (net (code "111") (name "Net-(DS6-A)") (class "Default")
      (node (ref "DS6") (pin "1") (pinfunction "A_1") (pintype "passive"))
      (node (ref "RP3") (pin "3") (pintype "passive"))
    )
    (net (code "112") (name "Net-(DS7-A)") (class "Default")
      (node (ref "DS7") (pin "1") (pinfunction "A_1") (pintype "passive"))
      (node (ref "RP3") (pin "4") (pintype "passive"))
    )
    (net (code "113") (name "Net-(DS8-A)") (class "Default")
      (node (ref "DS8") (pin "1") (pinfunction "A_1") (pintype "passive"))
      (node (ref "R10") (pin "1") (pinfunction "1_1") (pintype "passive"))
    )
    (net (code "114") (name "VBat") (class "Default")
      (node (ref "R3") (pin "2") (pinfunction "2_2") (pintype "passive"))
    )
    (net (code "115") (name "unconnected-(H1-Pad1)") (class "Default")
      (node (ref "H1") (pin "1") (pintype "passive"))
    )
    (net (code "116") (name "unconnected-(H2-Pad1)") (class "Default")
      (node (ref "H2") (pin "1") (pintype "passive"))
    )
    (net (code "117") (name "unconnected-(H3-Pad1)") (class "Default")
      (node (ref "H3") (pin "1") (pintype "passive"))
    )
    (net (code "118") (name "unconnected-(H4-Pad1)") (class "Default")
      (node (ref "H4") (pin "1") (pintype "passive"))
    )
    (net (code "119") (name "unconnected-(U1-AREF-Pad98)") (class "Default")
      (node (ref "U1") (pin "98") (pinfunction "AREF_98") (pintype "passive"))
    )
  )
)
